# Sheet1.net
KiCad netlist of a schematic drawn in Altium Designer
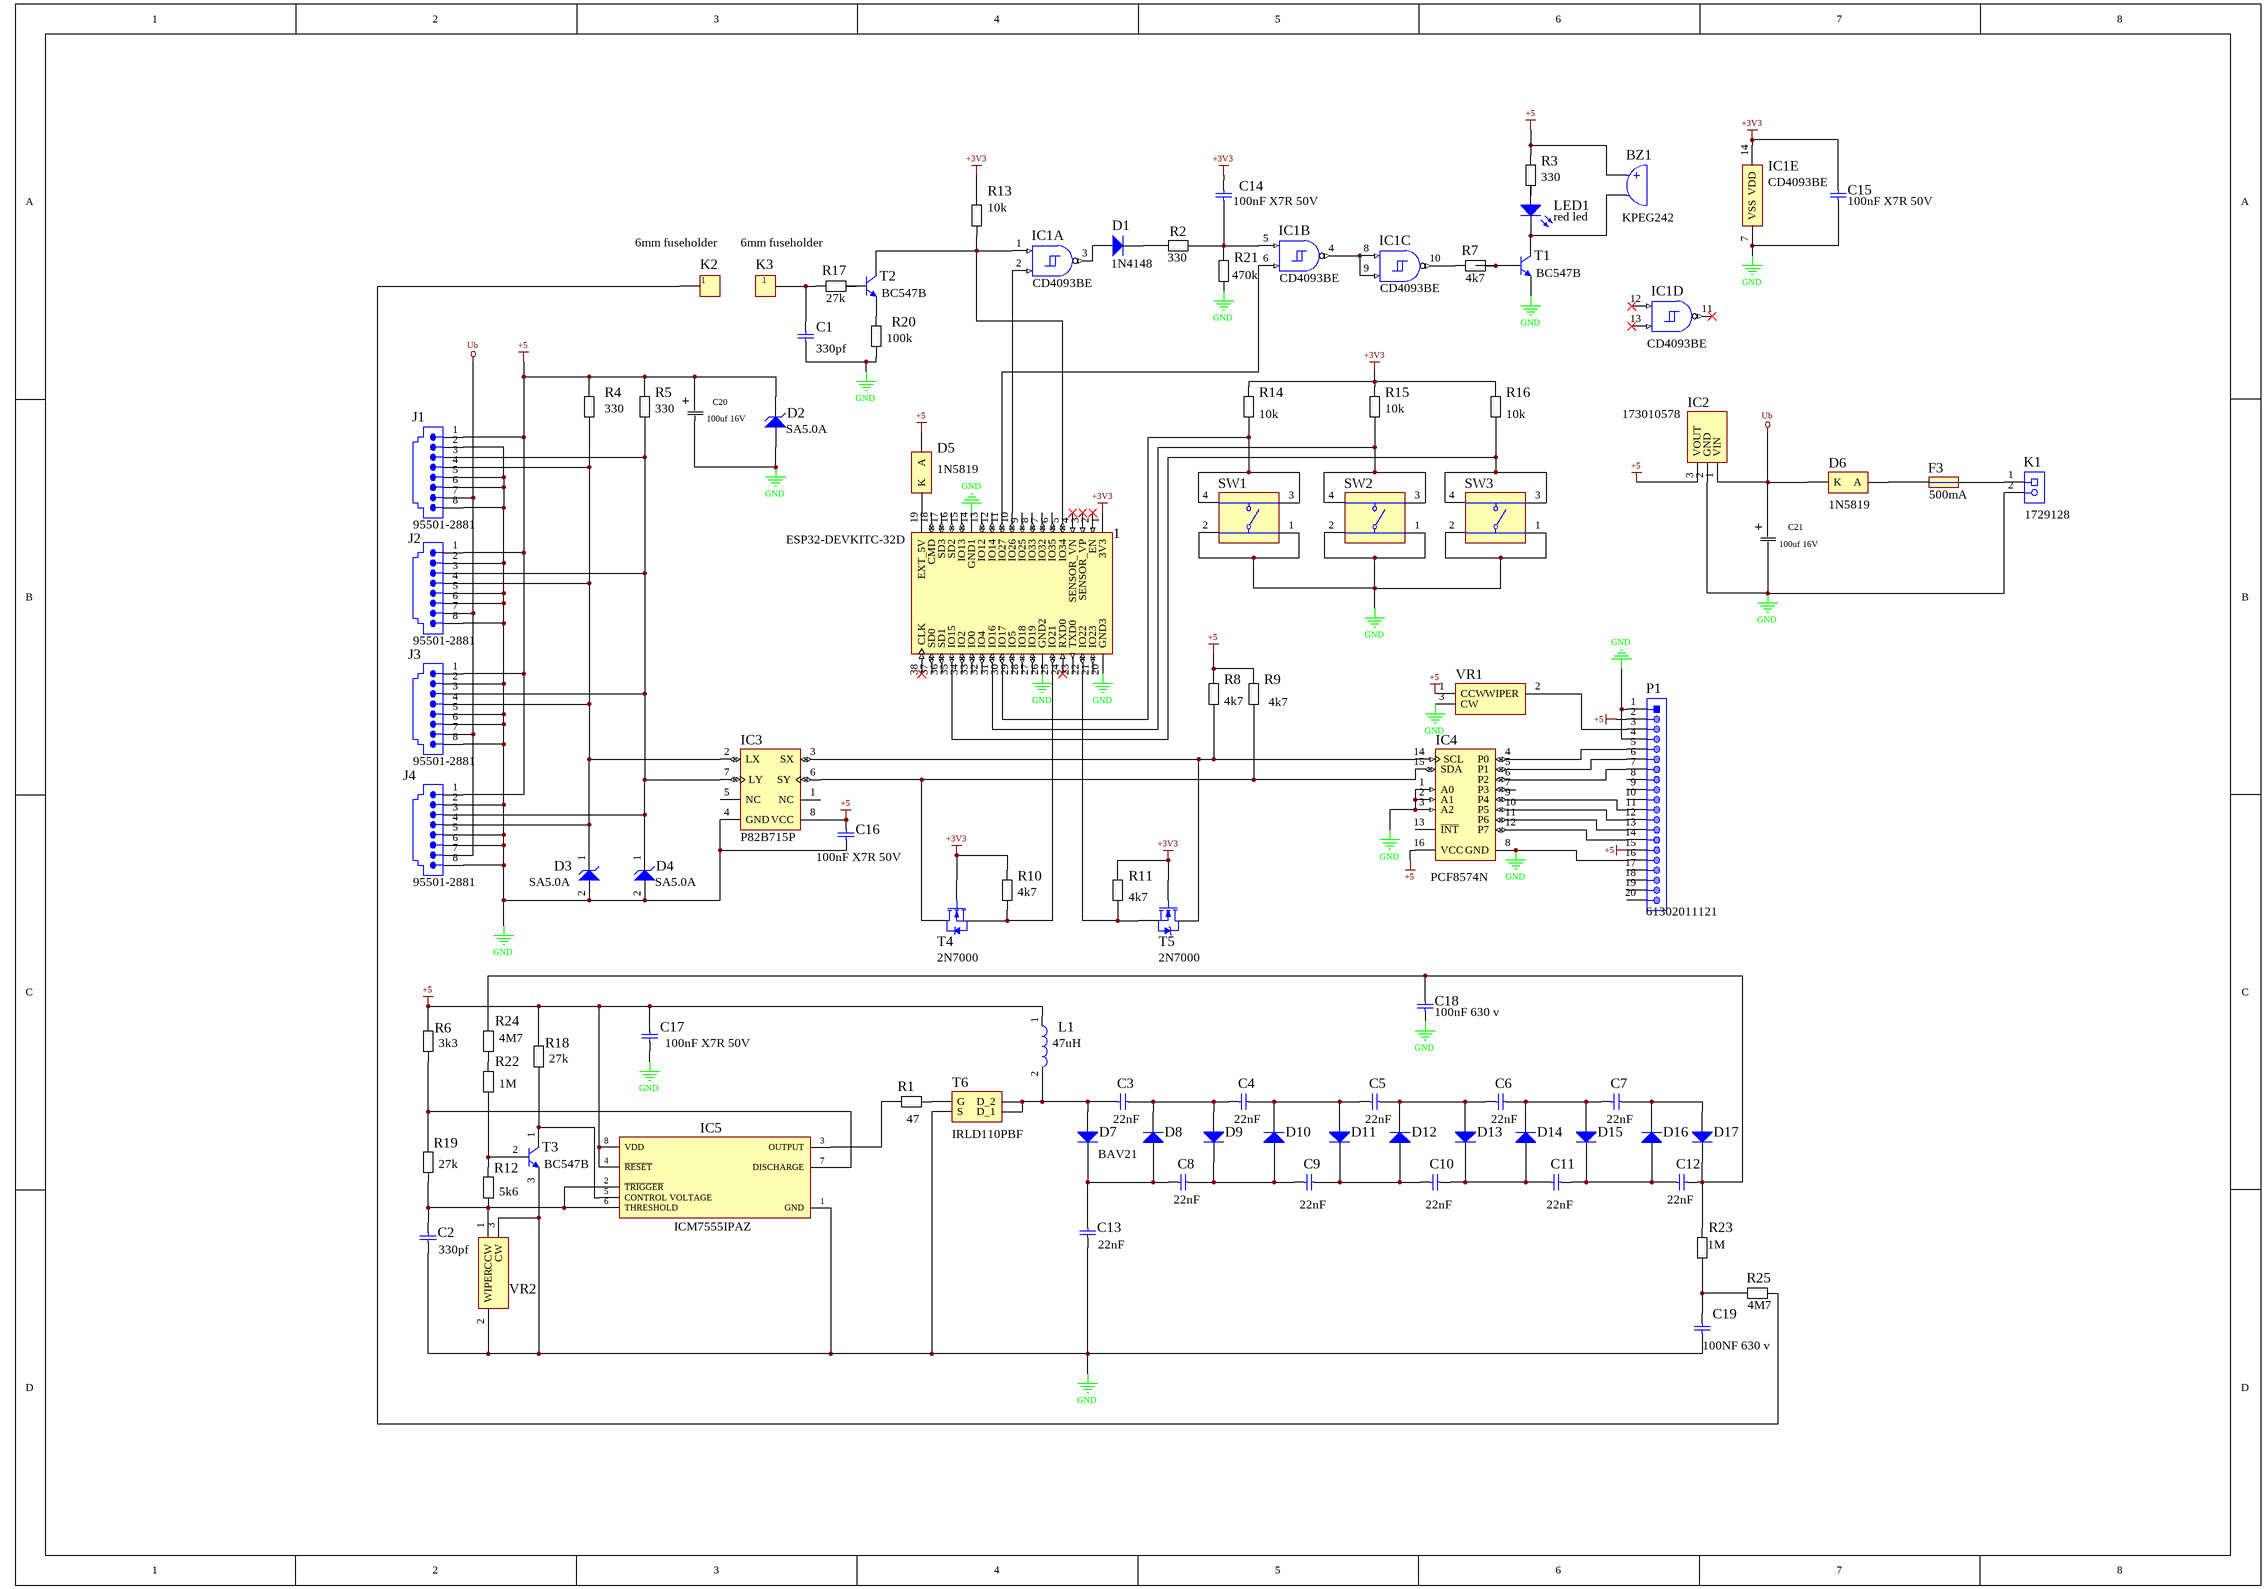
[diagram p0: Sheet1.SchDoc]

(export (version "E")
  (design (tool "Eeschema 10.0.6"))
  (components
    (comp (ref "1")
      (value "ESP32-DEVKITC-32D")
      (footprint "MODULE_ESP32-DEVKITC-32D")
      (description "EVAL BOARD FOR ESP-WROOM-32")
      (fields (field (name "MF") "Espressif Systems"))
      (libsource (lib "ESP32-DEVKITC-32D") (part "ESP32-DEVKITC-32D"))
    )
    (comp (ref "BZ1")
      (value "KPEG242")
      (footprint "KINGS-KPEG242-2")
      (description "Piezo Indicator, 4100 Hz, 3 to 16 V, -20 to 70 degC, 2-Pin THD, RoHS")
      (fields (field (name "PARTNUMBER") "KPE-242") (field (name "MANUFACTURER") "KingstateElectronicsCorp."))
      (libsource (lib "Altium Content Vault") (part "KINGS-KPEG242-2"))
    )
    (comp (ref "C1")
      (value "330pf")
      (footprint "CAPC2013X94X50ML20T25")
      (description "Chip Capacitor, Ceramic, 330 pF, 10%, 50 V, 0805, RoHS, Tape and Reel")
      (fields (field (name "MANUFACTURER") "AVX"))
      (libsource (lib "Altium Content Vault") (part "CAP-NP-2"))
    )
    (comp (ref "C2")
      (value "330pf")
      (footprint "CAPC2013X94X50ML20T25")
      (description "Chip Capacitor, Ceramic, 330 pF, 10%, 50 V, 0805, RoHS, Tape and Reel")
      (fields (field (name "MANUFACTURER") "AVX"))
      (libsource (lib "Altium Content Vault") (part "CAP-NP-2"))
    )
    (comp (ref "C3")
      (value "22nF")
      (footprint "VISH-BFC233820104-2_V")
      (fields (field (name "PARTNUMBER") "BFC233820104") (field (name "MANUFACTURER") "Vishay Semiconductor"))
      (libsource (lib "Altium Content Vault") (part "VISH-CAP-NP-2"))
    )
    (comp (ref "C4")
      (value "22nF")
      (footprint "VISH-BFC233820104-2_V")
      (fields (field (name "PARTNUMBER") "BFC233820104") (field (name "MANUFACTURER") "Vishay Semiconductor"))
      (libsource (lib "Altium Content Vault") (part "VISH-CAP-NP-2"))
    )
    (comp (ref "C5")
      (value "22nF")
      (footprint "VISH-BFC233820104-2_V")
      (fields (field (name "PARTNUMBER") "BFC233820104") (field (name "MANUFACTURER") "Vishay Semiconductor"))
      (libsource (lib "Altium Content Vault") (part "VISH-CAP-NP-2"))
    )
    (comp (ref "C6")
      (value "22nF")
      (footprint "VISH-BFC233820104-2_V")
      (fields (field (name "PARTNUMBER") "BFC233820104") (field (name "MANUFACTURER") "Vishay Semiconductor"))
      (libsource (lib "Altium Content Vault") (part "VISH-CAP-NP-2"))
    )
    (comp (ref "C7")
      (value "22nF")
      (footprint "VISH-BFC233820104-2_V")
      (fields (field (name "PARTNUMBER") "BFC233820104") (field (name "MANUFACTURER") "Vishay Semiconductor"))
      (libsource (lib "Altium Content Vault") (part "VISH-CAP-NP-2"))
    )
    (comp (ref "C8")
      (value "22nF")
      (footprint "VISH-BFC233820104-2_V")
      (fields (field (name "PARTNUMBER") "BFC233820104") (field (name "MANUFACTURER") "Vishay Semiconductor"))
      (libsource (lib "Altium Content Vault") (part "VISH-CAP-NP-2"))
    )
    (comp (ref "C9")
      (value "22nF")
      (footprint "VISH-BFC233820104-2_V")
      (fields (field (name "PARTNUMBER") "BFC233820104") (field (name "MANUFACTURER") "Vishay Semiconductor"))
      (libsource (lib "Altium Content Vault") (part "VISH-CAP-NP-2"))
    )
    (comp (ref "C10")
      (value "22nF")
      (footprint "VISH-BFC233820104-2_V")
      (fields (field (name "PARTNUMBER") "BFC233820104") (field (name "MANUFACTURER") "Vishay Semiconductor"))
      (libsource (lib "Altium Content Vault") (part "VISH-CAP-NP-2"))
    )
    (comp (ref "C11")
      (value "22nF")
      (footprint "VISH-BFC233820104-2_V")
      (fields (field (name "PARTNUMBER") "BFC233820104") (field (name "MANUFACTURER") "Vishay Semiconductor"))
      (libsource (lib "Altium Content Vault") (part "VISH-CAP-NP-2"))
    )
    (comp (ref "C12")
      (value "22nF")
      (footprint "VISH-BFC233820104-2_V")
      (fields (field (name "PARTNUMBER") "BFC233820104") (field (name "MANUFACTURER") "Vishay Semiconductor"))
      (libsource (lib "Altium Content Vault") (part "VISH-CAP-NP-2"))
    )
    (comp (ref "C13")
      (value "22nF")
      (footprint "VISH-BFC233820104-2_V")
      (fields (field (name "PARTNUMBER") "BFC233820104") (field (name "MANUFACTURER") "Vishay Semiconductor"))
      (libsource (lib "Altium Content Vault") (part "VISH-CAP-NP-2"))
    )
    (comp (ref "C14")
      (value "100nF X7R 50V")
      (footprint "CAPC2013X94X50ML20T25")
      (description "Chip Capacitor, Ceramic, 0.1 uF, 10%, 50 V, 0805, RoHS, Tape and Reel")
      (fields (field (name "MANUFACTURER") "AVX"))
      (libsource (lib "Altium Content Vault") (part "CAP-NP-2"))
    )
    (comp (ref "C15")
      (value "100nF X7R 50V")
      (footprint "CAPC2013X94X50ML20T25")
      (description "Chip Capacitor, Ceramic, 0.1 uF, 10%, 50 V, 0805, RoHS, Tape and Reel")
      (fields (field (name "MANUFACTURER") "AVX"))
      (libsource (lib "Altium Content Vault") (part "CAP-NP-2"))
    )
    (comp (ref "C16")
      (value "100nF X7R 50V")
      (footprint "CAPC2013X94X50ML20T25")
      (description "Chip Capacitor, Ceramic, 0.1 uF, 10%, 50 V, 0805, RoHS, Tape and Reel")
      (fields (field (name "MANUFACTURER") "AVX"))
      (libsource (lib "Altium Content Vault") (part "CAP-NP-2"))
    )
    (comp (ref "C17")
      (value "100nF X7R 50V")
      (footprint "CAPC2013X94X50ML20T25")
      (description "Chip Capacitor, Ceramic, 0.1 uF, 10%, 50 V, 0805, RoHS, Tape and Reel")
      (fields (field (name "MANUFACTURER") "AVX"))
      (libsource (lib "Altium Content Vault") (part "CAP-NP-2"))
    )
    (comp (ref "C18")
      (value "100nF 630 v")
      (footprint "CAPC1812(4532)125_M")
      (description "CAP 470nF 50V ±10% 1812 (4532 Metric) Thickness 1.25mm SMD")
      (fields (field (name "TOLERANCE") "Â±10%"))
      (libsource (lib "Altium Content Vault") (part "CAP"))
    )
    (comp (ref "C19")
      (value "100NF 630 v")
      (footprint "CAPC1812(4532)125_M")
      (description "CAP 470nF 50V ±10% 1812 (4532 Metric) Thickness 1.25mm SMD")
      (fields (field (name "TOLERANCE") "Â±10%"))
      (libsource (lib "Altium Content Vault") (part "CAP"))
    )
    (comp (ref "C20")
      (value "100uf 16V")
      (footprint "100uf 16V elco")
      (libsource (lib "Schlib2") (part "Component_1"))
    )
    (comp (ref "C21")
      (value "100uf 16V")
      (footprint "100uf 16V elco")
      (libsource (lib "Schlib2") (part "Component_1"))
    )
    (comp (ref "D1")
      (value "1N4148")
      (footprint "NXP-SOD27-2_V")
      (description "High-speed Diode, 100 V, 450 mA, 2-Pin SOD27, RoHS")
      (fields (field (name "MANUFACTURER") "NXP Semiconductors"))
      (libsource (lib "Altium Content Vault") (part "NXP-A1K2-2"))
    )
    (comp (ref "D2")
      (value "SA5.0A")
      (footprint "ONSC-AXIAL_LEAD-2-59AA-01_P")
      (fields (field (name "MANUFACTURER") "On Semiconductor"))
      (libsource (lib "Altium Content Vault") (part "ONSC-K1A2-2"))
    )
    (comp (ref "D3")
      (value "SA5.0A")
      (footprint "ONSC-AXIAL_LEAD-2-59AA-01_P")
      (fields (field (name "MANUFACTURER") "On Semiconductor"))
      (libsource (lib "") (part "ONSC-K1A2-2_1"))
    )
    (comp (ref "D4")
      (value "SA5.0A")
      (footprint "ONSC-AXIAL_LEAD-2-59AA-01_P")
      (fields (field (name "MANUFACTURER") "On Semiconductor"))
      (libsource (lib "") (part "ONSC-K1A2-2_1"))
    )
    (comp (ref "D5")
      (value "1N5819")
      (footprint "ONSC-AXIAL_LEAD-2-59-10_P")
      (description "Rectifier, 2-Pin Axial_Lead, Pb-Free, Bulk Bag")
      (fields (field (name "MANUFACTURER") "On Semiconductor"))
      (libsource (lib "Altium Content Vault") (part "ONSC-D-K1A2-2_A"))
    )
    (comp (ref "D6")
      (value "1N5819")
      (footprint "ONSC-AXIAL_LEAD-2-59-10_P")
      (description "Rectifier, 2-Pin Axial_Lead, Pb-Free, Bulk Bag")
      (fields (field (name "MANUFACTURER") "On Semiconductor"))
      (libsource (lib "") (part "ONSC-D-K1A2-2_A_1"))
    )
    (comp (ref "D7")
      (value "BAV21")
      (footprint "MCSM-DO-35-2")
      (description "BAV21TR Diode 250V 0.2A DO35")
      (fields (field (name "PARTNUMBER") "1N4148-1") (field (name "MANUFACTURER") "Microsemi"))
      (libsource (lib "Altium Content Vault") (part "D-AK-2"))
    )
    (comp (ref "D8")
      (value "BAV21")
      (footprint "MCSM-DO-35-2")
      (description "BAV21TR Diode 250V 0.2A DO35")
      (fields (field (name "PARTNUMBER") "1N4148-1") (field (name "MANUFACTURER") "Microsemi"))
      (libsource (lib "Altium Content Vault") (part "D-AK-2"))
    )
    (comp (ref "D9")
      (value "BAV21")
      (footprint "MCSM-DO-35-2")
      (description "BAV21TR Diode 250V 0.2A DO35")
      (fields (field (name "PARTNUMBER") "1N4148-1") (field (name "MANUFACTURER") "Microsemi"))
      (libsource (lib "Altium Content Vault") (part "D-AK-2"))
    )
    (comp (ref "D10")
      (value "BAV21")
      (footprint "MCSM-DO-35-2")
      (description "BAV21TR Diode 250V 0.2A DO35")
      (fields (field (name "PARTNUMBER") "1N4148-1") (field (name "MANUFACTURER") "Microsemi"))
      (libsource (lib "Altium Content Vault") (part "D-AK-2"))
    )
    (comp (ref "D11")
      (value "BAV21")
      (footprint "MCSM-DO-35-2")
      (description "BAV21TR Diode 250V 0.2A DO35")
      (fields (field (name "PARTNUMBER") "1N4148-1") (field (name "MANUFACTURER") "Microsemi"))
      (libsource (lib "Altium Content Vault") (part "D-AK-2"))
    )
    (comp (ref "D12")
      (value "BAV21")
      (footprint "MCSM-DO-35-2")
      (description "BAV21TR Diode 250V 0.2A DO35")
      (fields (field (name "PARTNUMBER") "1N4148-1") (field (name "MANUFACTURER") "Microsemi"))
      (libsource (lib "Altium Content Vault") (part "D-AK-2"))
    )
    (comp (ref "D13")
      (value "BAV21")
      (footprint "MCSM-DO-35-2")
      (description "BAV21TR Diode 250V 0.2A DO35")
      (fields (field (name "PARTNUMBER") "1N4148-1") (field (name "MANUFACTURER") "Microsemi"))
      (libsource (lib "Altium Content Vault") (part "D-AK-2"))
    )
    (comp (ref "D14")
      (value "BAV21")
      (footprint "MCSM-DO-35-2")
      (description "BAV21TR Diode 250V 0.2A DO35")
      (fields (field (name "PARTNUMBER") "1N4148-1") (field (name "MANUFACTURER") "Microsemi"))
      (libsource (lib "Altium Content Vault") (part "D-AK-2"))
    )
    (comp (ref "D15")
      (value "BAV21")
      (footprint "MCSM-DO-35-2")
      (description "BAV21TR Diode 250V 0.2A DO35")
      (fields (field (name "PARTNUMBER") "1N4148-1") (field (name "MANUFACTURER") "Microsemi"))
      (libsource (lib "Altium Content Vault") (part "D-AK-2"))
    )
    (comp (ref "D16")
      (value "BAV21")
      (footprint "MCSM-DO-35-2")
      (description "BAV21TR Diode 250V 0.2A DO35")
      (fields (field (name "PARTNUMBER") "1N4148-1") (field (name "MANUFACTURER") "Microsemi"))
      (libsource (lib "Altium Content Vault") (part "D-AK-2"))
    )
    (comp (ref "D17")
      (value "BAV21")
      (footprint "MCSM-DO-35-2")
      (description "BAV21TR Diode 250V 0.2A DO35")
      (fields (field (name "PARTNUMBER") "1N4148-1") (field (name "MANUFACTURER") "Microsemi"))
      (libsource (lib "Altium Content Vault") (part "D-AK-2"))
    )
    (comp (ref "F3")
      (value "500mA")
      (footprint "SamacSys:39211000000")
      (description "Fuse")
      (fields
        (field (name "MANUFACTURER_PART_NUMBER") "39211000000")
        (field (name "MOUSER PART NUMBER") "576-3921100000")
      )
      (libsource (lib "SamacSys") (part "39211000000"))
    )
    (comp (ref "IC1")
      (value "CD4093BE")
      (footprint "N0014A")
      (description "CMOS Quad 2-Input NAND Schmitt Triggers, N0014A, TUBE")
      (fields
        (field (name "MANUFACTURER") "Texas Instruments")
        (field (name "GENERIC PART NUMBER") "CD4093B")
      )
      (libsource (lib "") (part "TI-NAND-4-2IN-14_A-SCHMITT_1"))
    )
    (comp (ref "IC2")
      (value "173010578")
      (footprint "SamacSys:173010578")
      (description "Undefined or Miscellaneous")
      (fields (field (name "MOUSER2 PART NUMBER") "710-173010578"))
      (libsource (lib "SamacSys") (part "173010578"))
    )
    (comp (ref "IC3")
      (value "P82B715P")
      (footprint "P0008A")
      (description "I2C Bus Extender, 2 Channel Width, 3.0 to 12.0 V, -40 to 85 degC, 8-pin PDIP (P), Pb-Free (RoHS)")
      (fields (field (name "MANUFACTURER") "Texas Instruments"))
      (libsource (lib "Altium Content Vault") (part "TI-P82B715-PDIP_P-8"))
    )
    (comp (ref "IC4")
      (value "PCF8574N")
      (footprint "N0016A")
      (description "Remote 8-Bit I/O Expander for I2C-Bus, 2.5 to 6 V, -40 to 85 degC, 16-pin PDIP (N), Pb-Free (RoHS)")
      (fields (field (name "MANUFACTURER") "Texas Instruments"))
      (libsource (lib "Altium Content Vault") (part "TI-PCF8574-PDIP_N-16"))
    )
    (comp (ref "IC5")
      (value "ICM7555IPAZ")
      (footprint "Intersil_ICM7555IPAZ_0")
      (libsource (lib "IC_Intersil_ICM7555IPAZ_eec") (part "ICM7555IPAZ"))
    )
    (comp (ref "J1")
      (value "95501-2881")
      (footprint "MOLX-95501-2881_V")
      (description "Socket, PC Jack 8-Way, R/A Low-profile")
      (fields (field (name "MANUFACTURER") "Molex"))
      (libsource (lib "Altium Content Vault") (part "MOLX-95501-2881"))
    )
    (comp (ref "J2")
      (value "95501-2881")
      (footprint "MOLX-95501-2881_V")
      (description "Socket, PC Jack 8-Way, R/A Low-profile")
      (fields (field (name "MANUFACTURER") "Molex"))
      (libsource (lib "Altium Content Vault") (part "MOLX-95501-2881"))
    )
    (comp (ref "J3")
      (value "95501-2881")
      (footprint "MOLX-95501-2881_V")
      (description "Socket, PC Jack 8-Way, R/A Low-profile")
      (fields (field (name "MANUFACTURER") "Molex"))
      (libsource (lib "Altium Content Vault") (part "MOLX-95501-2881"))
    )
    (comp (ref "J4")
      (value "95501-2881")
      (footprint "MOLX-95501-2881_V")
      (description "Socket, PC Jack 8-Way, R/A Low-profile")
      (fields (field (name "MANUFACTURER") "Molex"))
      (libsource (lib "Altium Content Vault") (part "MOLX-95501-2881"))
    )
    (comp (ref "K1")
      (value "1729128")
      (footprint "PHOE-1729128-2_V")
      (description "PCB Terminal Block, 13.5 A, 400 V, 2-Pin THD, RoHS, Bulk")
      (fields (field (name "MANUFACTURER") "Phoenix Contact"))
      (libsource (lib "Altium Content Vault") (part "CN-2P-F-R2"))
    )
    (comp (ref "K2")
      (value "6mm fuseholder")
      (footprint "FP-102-MFG")
      (description "FUSE CLIP CARTRIDGE 250V 15A PCB")
      (fields
        (field (name "MANUFACTURER") "Littelfuse Inc")
        (field (name "OCTOPART") "https://octopart.com/01020071z-littelfuse-18837869")
      )
      (libsource (lib "Altium Content Vault") (part "600373309f0643ccfefc365bd0e8f7b"))
    )
    (comp (ref "K3")
      (value "6mm fuseholder")
      (footprint "FP-102-MFG")
      (description "FUSE CLIP CARTRIDGE 250V 15A PCB")
      (fields
        (field (name "MANUFACTURER") "Littelfuse Inc")
        (field (name "OCTOPART") "https://octopart.com/01020071z-littelfuse-18837869")
      )
      (libsource (lib "") (part "600373309f0643ccfefc365bd0e8f7b_1"))
    )
    (comp (ref "L1")
      (value "47uH")
      (footprint "WE-TI-LS")
      (description "Radial Leaded Wire Wound Inductor WE-TI, L = 100 µH")
      (libsource (lib "Altium Content Vault") (part "PAS-IND-INDUCTOR-2"))
    )
    (comp (ref "LED1")
      (value "red led")
      (footprint "Type 3mm")
      (description "THT LED round mono-color color lens, WL-TMRW, Super Red")
      (fields (field (name "PARTNUMBER") "151031SS06000") (field (name "MANUFACTURER") "Wuerth Elektronik"))
      (libsource (lib "Altium Content Vault") (part "WE-LED_K1A2-2"))
    )
    (comp (ref "P1")
      (value "61302011121")
      (footprint "61302011121")
      (description "THT Vertical Pin Header WR-PHD, Pitch 2.54 mm, Single Row, 20 pins")
      (fields (field (name "MANUFACTURER") "Wurth Elektronik") (field (name "PUBLISHER") "WurthElektronik"))
      (libsource (lib "Altium Content Vault") (part "WE-CN-1P-M-R20"))
    )
    (comp (ref "R1")
      (value "47")
      (footprint "FP-RC1206-IPC_C")
      (libsource (lib "") (part "1206 weerstand_3"))
    )
    (comp (ref "R2")
      (value "330")
      (footprint "FP-RC1206-IPC_C")
      (libsource (lib "") (part "1206 weerstand_1"))
    )
    (comp (ref "R3")
      (value "330")
      (footprint "FP-RC1206-IPC_C")
      (libsource (lib "") (part "1206 weerstand_2"))
    )
    (comp (ref "R4")
      (value "330")
      (footprint "FP-RC1206-IPC_C")
      (libsource (lib "Schlib1") (part "1206 weerstand"))
    )
    (comp (ref "R5")
      (value "330")
      (footprint "FP-RC1206-IPC_C")
      (libsource (lib "Schlib1") (part "1206 weerstand"))
    )
    (comp (ref "R6")
      (value "3k3")
      (footprint "FP-RC1206-IPC_C")
      (libsource (lib "Schlib1") (part "1206 weerstand"))
    )
    (comp (ref "R7")
      (value "4k7")
      (footprint "FP-RC1206-IPC_C")
      (libsource (lib "") (part "1206 weerstand_3"))
    )
    (comp (ref "R8")
      (value "4k7")
      (footprint "FP-RC1206-IPC_C")
      (libsource (lib "Schlib1") (part "1206 weerstand"))
    )
    (comp (ref "R9")
      (value "4k7")
      (footprint "FP-RC1206-IPC_C")
      (libsource (lib "Schlib1") (part "1206 weerstand"))
    )
    (comp (ref "R10")
      (value "4k7")
      (footprint "FP-RC1206-IPC_C")
      (libsource (lib "Schlib1") (part "1206 weerstand"))
    )
    (comp (ref "R11")
      (value "4k7")
      (footprint "FP-RC1206-IPC_C")
      (libsource (lib "") (part "1206 weerstand_1"))
    )
    (comp (ref "R12")
      (value "5k6")
      (footprint "FP-RC1206-IPC_C")
      (libsource (lib "Schlib1") (part "1206 weerstand"))
    )
    (comp (ref "R13")
      (value "10k")
      (footprint "FP-RC1206-IPC_C")
      (libsource (lib "") (part "1206 weerstand_2"))
    )
    (comp (ref "R14")
      (value "10k")
      (footprint "FP-RC1206-IPC_C")
      (libsource (lib "Schlib1") (part "1206 weerstand"))
    )
    (comp (ref "R15")
      (value "10k")
      (footprint "FP-RC1206-IPC_C")
      (libsource (lib "Schlib1") (part "1206 weerstand"))
    )
    (comp (ref "R16")
      (value "10k")
      (footprint "FP-RC1206-IPC_C")
      (libsource (lib "Schlib1") (part "1206 weerstand"))
    )
    (comp (ref "R17")
      (value "27k")
      (footprint "FP-RC1206-IPC_C")
      (libsource (lib "") (part "1206 weerstand_3"))
    )
    (comp (ref "R18")
      (value "27k")
      (footprint "FP-RC1206-IPC_C")
      (libsource (lib "Schlib1") (part "1206 weerstand"))
    )
    (comp (ref "R19")
      (value "27k")
      (footprint "FP-RC1206-IPC_C")
      (libsource (lib "Schlib1") (part "1206 weerstand"))
    )
    (comp (ref "R20")
      (value "100k")
      (footprint "FP-RC1206-IPC_C")
      (libsource (lib "") (part "1206 weerstand_2"))
    )
    (comp (ref "R21")
      (value "470k")
      (footprint "FP-RC1206-IPC_C")
      (libsource (lib "Schlib1") (part "1206 weerstand"))
    )
    (comp (ref "R22")
      (value "1M")
      (footprint "RES_VR25")
      (description "No Description Available")
      (fields
        (field (name "MANUFACTURER_PART_NUMBER") "VR25000001004JA100")
        (field (name "COPYRIGHT") "Copyright (C) 2018 Accelerated Designs. All rights reserved")
      )
      (libsource (lib "2021-03-05_17-49-49") (part "VR25000001004JA100"))
    )
    (comp (ref "R23")
      (value "1M")
      (footprint "RES_VR25")
      (description "No Description Available")
      (fields
        (field (name "MANUFACTURER_PART_NUMBER") "VR25000001004JA100")
        (field (name "COPYRIGHT") "Copyright (C) 2018 Accelerated Designs. All rights reserved")
      )
      (libsource (lib "2021-03-05_17-49-49") (part "VR25000001004JA100"))
    )
    (comp (ref "R24")
      (value "4M7")
      (footprint "RES_VR25")
      (description "No Description Available")
      (fields
        (field (name "MANUFACTURER_PART_NUMBER") "VR25000001004JA100")
        (field (name "COPYRIGHT") "Copyright (C) 2018 Accelerated Designs. All rights reserved")
      )
      (libsource (lib "2021-03-05_17-49-49") (part "VR25000001004JA100"))
    )
    (comp (ref "R25")
      (value "4M7")
      (footprint "RES_VR25")
      (description "No Description Available")
      (fields
        (field (name "MANUFACTURER_PART_NUMBER") "VR25000001004JA100")
        (field (name "COPYRIGHT") "Copyright (C) 2018 Accelerated Designs. All rights reserved")
      )
      (libsource (lib "") (part "VR25000001004JA100_1"))
    )
    (comp (ref "SW1")
      (value "tactile switch 10mm")
      (footprint "TECO-1825910-6_V")
      (description "Tact Switch, SPST-NO, 0.05 A, -35 to 85 degC, 4-Pin THD, RoHS, Bulk")
      (fields (field (name "PART NO") "1825910-6") (field (name "MANUFACTURER") "TE Connectivity"))
      (libsource (lib "Altium Content Vault") (part "SW-SPST-4_A"))
    )
    (comp (ref "SW2")
      (value "tactile switch 10mm")
      (footprint "TECO-1825910-6_V")
      (description "Tact Switch, SPST-NO, 0.05 A, -35 to 85 degC, 4-Pin THD, RoHS, Bulk")
      (fields (field (name "PART NO") "1825910-6") (field (name "MANUFACTURER") "TE Connectivity"))
      (libsource (lib "Altium Content Vault") (part "SW-SPST-4_A"))
    )
    (comp (ref "SW3")
      (value "tactile switch 10mm")
      (footprint "TECO-1825910-6_V")
      (description "Tact Switch, SPST-NO, 0.05 A, -35 to 85 degC, 4-Pin THD, RoHS, Bulk")
      (fields (field (name "PART NO") "1825910-6") (field (name "MANUFACTURER") "TE Connectivity"))
      (libsource (lib "Altium Content Vault") (part "SW-SPST-4_A"))
    )
    (comp (ref "T1")
      (value "BC547B")
      (footprint "ONSC-TO-92-3-29-11")
      (description "Amplifier Transistor, NPN Silicon, 3-Pin TO-92, Bulk Box")
      (fields (field (name "MANUFACTURER") "On Semiconductor"))
      (libsource (lib "Altium Content Vault") (part "ONSC-NPN-C1B2E3-3"))
    )
    (comp (ref "T2")
      (value "BC547B")
      (footprint "ONSC-TO-92-3-29-11")
      (description "Amplifier Transistor, NPN Silicon, 3-Pin TO-92, Bulk Box")
      (fields (field (name "MANUFACTURER") "On Semiconductor"))
      (libsource (lib "Altium Content Vault") (part "ONSC-NPN-C1B2E3-3"))
    )
    (comp (ref "T3")
      (value "BC547B")
      (footprint "ONSC-TO-92-3-29-11")
      (description "Amplifier Transistor, NPN Silicon, 3-Pin TO-92, Bulk Box")
      (fields (field (name "MANUFACTURER") "On Semiconductor"))
      (libsource (lib "") (part "ONSC-NPN-C1B2E3-3_1"))
    )
    (comp (ref "T4")
      (value "2N7000")
      (footprint "ONSC-TO-92-3-29-11")
      (description "Small Signal MOSFET, 200 mA, 60 V, N-Channel, 3-Pin TO-92, Bulk Box")
      (fields (field (name "MANUFACTURER") "On Semiconductor"))
      (libsource (lib "Altium Content Vault") (part "ONSC-NMOS-S1G2D3-3"))
    )
    (comp (ref "T5")
      (value "2N7000")
      (footprint "ONSC-TO-92-3-29-11")
      (description "Small Signal MOSFET, 200 mA, 60 V, N-Channel, 3-Pin TO-92, Bulk Box")
      (fields (field (name "MANUFACTURER") "On Semiconductor"))
      (libsource (lib "Altium Content Vault") (part "ONSC-NMOS-S1G2D3-3"))
    )
    (comp (ref "T6")
      (value "IRLD110PBF")
      (footprint "SamacSys:DIP920W60P254L490H337Q4N")
      (description "MOSFET (N-Channel)")
      (fields (field (name "MOUSER PART NUMBER") "844-IRLD110PBF"))
      (libsource (lib "SamacSys") (part "IRLD110PBF"))
    )
    (comp (ref "VR1")
      (value "~")
      (footprint "RM065102")
      (description "Variable Resistor")
      (fields (field (name "MANUFACTURER_PART_NUMBER") "RM-065-102"))
      (libsource (lib "") (part "RM-065-102_1"))
    )
    (comp (ref "VR2")
      (value "RM-065-102")
      (footprint "SamacSys:RM065102")
      (description "Variable Resistor")
      (libsource (lib "SamacSys") (part "RM-065-102"))
    )
  )
  (nets
    (net (code "1") (name "+3V3") (class "Default")
      (node (ref "1") (pin "1") (pinfunction "3V3_1") (pintype "power_in"))
      (node (ref "C14") (pin "2") (pinfunction "2_2") (pintype "passive"))
      (node (ref "C15") (pin "2") (pinfunction "2_2") (pintype "passive"))
      (node (ref "IC1") (pin "14") (pinfunction "VDD_14") (pintype "power_in"))
      (node (ref "R10") (pin "2") (pintype "passive"))
      (node (ref "R11") (pin "2") (pintype "passive"))
      (node (ref "R13") (pin "1") (pintype "passive"))
      (node (ref "R14") (pin "2") (pintype "passive"))
      (node (ref "R15") (pin "2") (pintype "passive"))
      (node (ref "R16") (pin "2") (pintype "passive"))
      (node (ref "T4") (pin "2") (pinfunction "G_2") (pintype "passive"))
      (node (ref "T5") (pin "2") (pinfunction "G_2") (pintype "passive"))
    )
    (net (code "2") (name "+5") (class "Default")
      (node (ref "BZ1") (pin "1") (pinfunction "1_1") (pintype "passive"))
      (node (ref "C16") (pin "2") (pinfunction "2_2") (pintype "passive"))
      (node (ref "C17") (pin "2") (pinfunction "2_2") (pintype "passive"))
      (node (ref "D2") (pin "1") (pinfunction "K_1") (pintype "passive"))
      (node (ref "D5") (pin "2") (pinfunction "A_2") (pintype "passive"))
      (node (ref "IC2") (pin "3") (pinfunction "VOUT_3") (pintype "passive"))
      (node (ref "IC3") (pin "8") (pinfunction "VCC_8") (pintype "power_in"))
      (node (ref "IC4") (pin "16") (pinfunction "VCC_16") (pintype "power_in"))
      (node (ref "IC5") (pin "4") (pinfunction "~{RESET}_4") (pintype "passive"))
      (node (ref "IC5") (pin "8") (pinfunction "VDD_8") (pintype "passive"))
      (node (ref "J1") (pin "1") (pinfunction "1_1") (pintype "passive"))
      (node (ref "J2") (pin "1") (pinfunction "1_1") (pintype "passive"))
      (node (ref "J3") (pin "1") (pinfunction "1_1") (pintype "passive"))
      (node (ref "J4") (pin "1") (pinfunction "1_1") (pintype "passive"))
      (node (ref "L1") (pin "1") (pinfunction "1_1") (pintype "passive"))
      (node (ref "P1") (pin "15") (pinfunction "15_15") (pintype "passive"))
      (node (ref "P1") (pin "2") (pinfunction "2_2") (pintype "passive"))
      (node (ref "R18") (pin "2") (pintype "passive"))
      (node (ref "R3") (pin "1") (pintype "passive"))
      (node (ref "R4") (pin "2") (pintype "passive"))
      (node (ref "R5") (pin "2") (pintype "passive"))
      (node (ref "R6") (pin "2") (pintype "passive"))
      (node (ref "R8") (pin "2") (pintype "passive"))
      (node (ref "R9") (pin "2") (pintype "passive"))
      (node (ref "VR1") (pin "1") (pinfunction "CCW_1") (pintype "passive"))
    )
    (net (code "3") (name "GND") (class "Default")
      (node (ref "1") (pin "14") (pinfunction "GND1_14") (pintype "power_in"))
      (node (ref "1") (pin "20") (pinfunction "GND3_20") (pintype "power_in"))
      (node (ref "1") (pin "26") (pinfunction "GND2_26") (pintype "power_in"))
      (node (ref "C1") (pin "1") (pinfunction "1_1") (pintype "passive"))
      (node (ref "C13") (pin "1") (pinfunction "1_1") (pintype "passive"))
      (node (ref "C15") (pin "1") (pinfunction "1_1") (pintype "passive"))
      (node (ref "C16") (pin "1") (pinfunction "1_1") (pintype "passive"))
      (node (ref "C17") (pin "1") (pinfunction "1_1") (pintype "passive"))
      (node (ref "C18") (pin "1") (pinfunction "1_1") (pintype "passive"))
      (node (ref "C19") (pin "1") (pinfunction "1_1") (pintype "passive"))
      (node (ref "C2") (pin "1") (pinfunction "1_1") (pintype "passive"))
      (node (ref "D2") (pin "2") (pinfunction "A_2") (pintype "passive"))
      (node (ref "D3") (pin "2") (pinfunction "A_2") (pintype "passive"))
      (node (ref "D4") (pin "2") (pinfunction "A_2") (pintype "passive"))
      (node (ref "IC1") (pin "7") (pinfunction "VSS_7") (pintype "power_in"))
      (node (ref "IC2") (pin "2") (pinfunction "GND_2") (pintype "passive"))
      (node (ref "IC3") (pin "4") (pinfunction "GND_4") (pintype "power_in"))
      (node (ref "IC4") (pin "1") (pinfunction "A0_1") (pintype "input"))
      (node (ref "IC4") (pin "2") (pinfunction "A1_2") (pintype "input"))
      (node (ref "IC4") (pin "3") (pinfunction "A2_3") (pintype "input"))
      (node (ref "IC4") (pin "8") (pinfunction "GND_8") (pintype "power_in"))
      (node (ref "IC5") (pin "1") (pinfunction "GND_1") (pintype "passive"))
      (node (ref "J1") (pin "2") (pinfunction "2_2") (pintype "passive"))
      (node (ref "J1") (pin "5") (pinfunction "5_5") (pintype "passive"))
      (node (ref "J1") (pin "6") (pinfunction "6_6") (pintype "passive"))
      (node (ref "J1") (pin "8") (pinfunction "8_8") (pintype "passive"))
      (node (ref "J2") (pin "2") (pinfunction "2_2") (pintype "passive"))
      (node (ref "J2") (pin "5") (pinfunction "5_5") (pintype "passive"))
      (node (ref "J2") (pin "6") (pinfunction "6_6") (pintype "passive"))
      (node (ref "J2") (pin "8") (pinfunction "8_8") (pintype "passive"))
      (node (ref "J3") (pin "2") (pinfunction "2_2") (pintype "passive"))
      (node (ref "J3") (pin "5") (pinfunction "5_5") (pintype "passive"))
      (node (ref "J3") (pin "6") (pinfunction "6_6") (pintype "passive"))
      (node (ref "J3") (pin "8") (pinfunction "8_8") (pintype "passive"))
      (node (ref "J4") (pin "2") (pinfunction "2_2") (pintype "passive"))
      (node (ref "J4") (pin "5") (pinfunction "5_5") (pintype "passive"))
      (node (ref "J4") (pin "6") (pinfunction "6_6") (pintype "passive"))
      (node (ref "J4") (pin "8") (pinfunction "8_8") (pintype "passive"))
      (node (ref "K1") (pin "2") (pinfunction "2_2") (pintype "passive"))
      (node (ref "P1") (pin "1") (pinfunction "1_1") (pintype "passive"))
      (node (ref "P1") (pin "16") (pinfunction "16_16") (pintype "passive"))
      (node (ref "P1") (pin "4") (pinfunction "4_4") (pintype "passive"))
      (node (ref "R20") (pin "2") (pintype "passive"))
      (node (ref "R21") (pin "1") (pintype "passive"))
      (node (ref "SW1") (pin "1") (pinfunction "1_1") (pintype "passive"))
      (node (ref "SW1") (pin "2") (pinfunction "2_2") (pintype "passive"))
      (node (ref "SW2") (pin "1") (pinfunction "1_1") (pintype "passive"))
      (node (ref "SW2") (pin "2") (pinfunction "2_2") (pintype "passive"))
      (node (ref "SW3") (pin "1") (pinfunction "1_1") (pintype "passive"))
      (node (ref "SW3") (pin "2") (pinfunction "2_2") (pintype "passive"))
      (node (ref "T1") (pin "3") (pinfunction "E_3") (pintype "passive"))
      (node (ref "T3") (pin "3") (pinfunction "E_3") (pintype "passive"))
      (node (ref "T6") (pin "2") (pinfunction "S_2") (pintype "passive"))
      (node (ref "VR1") (pin "3") (pinfunction "CW_3") (pintype "passive"))
      (node (ref "VR2") (pin "2") (pinfunction "WIPER_2") (pintype "passive"))
      (node (ref "VR2") (pin "3") (pinfunction "CW_3") (pintype "passive"))
    )
    (net (code "4") (name "Net-(1-EXT_5V)") (class "Default")
      (node (ref "1") (pin "19") (pinfunction "EXT_5V_19") (pintype "power_in"))
      (node (ref "D5") (pin "1") (pinfunction "K_1") (pintype "passive"))
    )
    (net (code "5") (name "Net-(1-IO15)") (class "Default")
      (node (ref "1") (pin "35") (pinfunction "IO15_35") (pintype "bidirectional"))
      (node (ref "R16") (pin "1") (pintype "passive"))
      (node (ref "SW3") (pin "3") (pinfunction "3_3") (pintype "passive"))
      (node (ref "SW3") (pin "4") (pinfunction "4_4") (pintype "passive"))
    )
    (net (code "6") (name "Net-(1-IO16)") (class "Default")
      (node (ref "1") (pin "31") (pinfunction "IO16_31") (pintype "bidirectional"))
      (node (ref "R15") (pin "1") (pintype "passive"))
      (node (ref "SW2") (pin "3") (pinfunction "3_3") (pintype "passive"))
      (node (ref "SW2") (pin "4") (pinfunction "4_4") (pintype "passive"))
    )
    (net (code "7") (name "Net-(1-IO17)") (class "Default")
      (node (ref "1") (pin "30") (pinfunction "IO17_30") (pintype "bidirectional"))
      (node (ref "R14") (pin "1") (pintype "passive"))
      (node (ref "SW1") (pin "3") (pinfunction "3_3") (pintype "passive"))
      (node (ref "SW1") (pin "4") (pinfunction "4_4") (pintype "passive"))
    )
    (net (code "8") (name "Net-(1-IO21)") (class "Default")
      (node (ref "1") (pin "25") (pinfunction "IO21_25") (pintype "bidirectional"))
      (node (ref "R10") (pin "1") (pintype "passive"))
      (node (ref "T4") (pin "1") (pinfunction "S_1") (pintype "passive"))
    )
    (net (code "9") (name "Net-(1-IO22)") (class "Default")
      (node (ref "1") (pin "22") (pinfunction "IO22_22") (pintype "bidirectional"))
      (node (ref "R11") (pin "1") (pintype "passive"))
      (node (ref "T5") (pin "1") (pinfunction "S_1") (pintype "passive"))
    )
    (net (code "10") (name "Net-(1-IO26)") (class "Default")
      (node (ref "1") (pin "10") (pinfunction "IO26_10") (pintype "bidirectional"))
      (node (ref "IC1") (pin "2") (pinfunction "B_2") (pintype "input"))
    )
    (net (code "11") (name "Net-(1-IO27)") (class "Default")
      (node (ref "1") (pin "11") (pinfunction "IO27_11") (pintype "bidirectional"))
      (node (ref "IC1") (pin "6") (pinfunction "D_6") (pintype "input"))
    )
    (net (code "12") (name "Net-(1-IO34)") (class "Default")
      (node (ref "1") (pin "5") (pinfunction "IO34_5") (pintype "bidirectional"))
      (node (ref "IC1") (pin "1") (pinfunction "A_1") (pintype "input"))
      (node (ref "R13") (pin "2") (pintype "passive"))
      (node (ref "T2") (pin "1") (pinfunction "C_1") (pintype "passive"))
    )
    (net (code "13") (name "Net-(C1-Pad2)") (class "Default")
      (node (ref "C1") (pin "2") (pinfunction "2_2") (pintype "passive"))
      (node (ref "K3") (pin "1") (pinfunction "1_1") (pintype "passive"))
      (node (ref "R17") (pin "2") (pintype "passive"))
    )
    (net (code "14") (name "Net-(C19-Pad2)") (class "Default")
      (node (ref "C19") (pin "2") (pinfunction "2_2") (pintype "passive"))
      (node (ref "R23") (pin "1") (pintype "passive"))
      (node (ref "R25") (pin "1") (pintype "passive"))
    )
    (net (code "15") (name "Net-(D1-A)") (class "Default")
      (node (ref "D1") (pin "1") (pinfunction "A_1") (pintype "passive"))
      (node (ref "IC1") (pin "3") (pinfunction "J_3") (pintype "output"))
    )
    (net (code "16") (name "Net-(D1-K)") (class "Default")
      (node (ref "D1") (pin "2") (pinfunction "K_2") (pintype "passive"))
      (node (ref "R2") (pin "1") (pintype "passive"))
    )
    (net (code "17") (name "Net-(D3-K)") (class "Default")
      (node (ref "D3") (pin "1") (pinfunction "K_1") (pintype "passive"))
      (node (ref "IC3") (pin "2") (pinfunction "LX_2") (pintype "bidirectional"))
      (node (ref "J1") (pin "4") (pinfunction "4_4") (pintype "passive"))
      (node (ref "J2") (pin "4") (pinfunction "4_4") (pintype "passive"))
      (node (ref "J3") (pin "4") (pinfunction "4_4") (pintype "passive"))
      (node (ref "J4") (pin "4") (pinfunction "4_4") (pintype "passive"))
      (node (ref "R4") (pin "1") (pintype "passive"))
    )
    (net (code "18") (name "Net-(D4-K)") (class "Default")
      (node (ref "D4") (pin "1") (pinfunction "K_1") (pintype "passive"))
      (node (ref "IC3") (pin "7") (pinfunction "LY_7") (pintype "bidirectional"))
      (node (ref "J1") (pin "3") (pinfunction "3_3") (pintype "passive"))
      (node (ref "J2") (pin "3") (pinfunction "3_3") (pintype "passive"))
      (node (ref "J3") (pin "3") (pinfunction "3_3") (pintype "passive"))
      (node (ref "J4") (pin "3") (pinfunction "3_3") (pintype "passive"))
      (node (ref "R5") (pin "1") (pintype "passive"))
    )
    (net (code "19") (name "Net-(D6-A)") (class "Default")
      (node (ref "D6") (pin "2") (pinfunction "A_2") (pintype "passive"))
      (node (ref "F3") (pin "1") (pinfunction "1_1") (pintype "passive"))
    )
    (net (code "20") (name "Net-(D7-A)") (class "Default")
      (node (ref "C3") (pin "1") (pinfunction "1_1") (pintype "passive"))
      (node (ref "D7") (pin "1") (pinfunction "A_1") (pintype "passive"))
      (node (ref "L1") (pin "2") (pinfunction "2_2") (pintype "passive"))
      (node (ref "T6") (pin "3") (pinfunction "D_1_3") (pintype "passive"))
      (node (ref "T6") (pin "4") (pinfunction "D_2_4") (pintype "passive"))
    )
    (net (code "21") (name "Net-(D7-K)") (class "Default")
      (node (ref "C13") (pin "2") (pinfunction "2_2") (pintype "passive"))
      (node (ref "C8") (pin "1") (pinfunction "1_1") (pintype "passive"))
      (node (ref "D7") (pin "2") (pinfunction "K_2") (pintype "passive"))
      (node (ref "D8") (pin "1") (pinfunction "A_1") (pintype "passive"))
    )
    (net (code "22") (name "Net-(D8-K)") (class "Default")
      (node (ref "C3") (pin "2") (pinfunction "2_2") (pintype "passive"))
      (node (ref "C4") (pin "1") (pinfunction "1_1") (pintype "passive"))
      (node (ref "D8") (pin "2") (pinfunction "K_2") (pintype "passive"))
      (node (ref "D9") (pin "1") (pinfunction "A_1") (pintype "passive"))
    )
    (net (code "23") (name "Net-(D10-A)") (class "Default")
      (node (ref "C8") (pin "2") (pinfunction "2_2") (pintype "passive"))
      (node (ref "C9") (pin "1") (pinfunction "1_1") (pintype "passive"))
      (node (ref "D10") (pin "1") (pinfunction "A_1") (pintype "passive"))
      (node (ref "D9") (pin "2") (pinfunction "K_2") (pintype "passive"))
    )
    (net (code "24") (name "Net-(D10-K)") (class "Default")
      (node (ref "C4") (pin "2") (pinfunction "2_2") (pintype "passive"))
      (node (ref "C5") (pin "1") (pinfunction "1_1") (pintype "passive"))
      (node (ref "D10") (pin "2") (pinfunction "K_2") (pintype "passive"))
      (node (ref "D11") (pin "1") (pinfunction "A_1") (pintype "passive"))
    )
    (net (code "25") (name "Net-(D11-K)") (class "Default")
      (node (ref "C10") (pin "1") (pinfunction "1_1") (pintype "passive"))
      (node (ref "C9") (pin "2") (pinfunction "2_2") (pintype "passive"))
      (node (ref "D11") (pin "2") (pinfunction "K_2") (pintype "passive"))
      (node (ref "D12") (pin "1") (pinfunction "A_1") (pintype "passive"))
    )
    (net (code "26") (name "Net-(D12-K)") (class "Default")
      (node (ref "C5") (pin "2") (pinfunction "2_2") (pintype "passive"))
      (node (ref "C6") (pin "1") (pinfunction "1_1") (pintype "passive"))
      (node (ref "D12") (pin "2") (pinfunction "K_2") (pintype "passive"))
      (node (ref "D13") (pin "1") (pinfunction "A_1") (pintype "passive"))
    )
    (net (code "27") (name "Net-(D13-K)") (class "Default")
      (node (ref "C10") (pin "2") (pinfunction "2_2") (pintype "passive"))
      (node (ref "C11") (pin "1") (pinfunction "1_1") (pintype "passive"))
      (node (ref "D13") (pin "2") (pinfunction "K_2") (pintype "passive"))
      (node (ref "D14") (pin "1") (pinfunction "A_1") (pintype "passive"))
    )
    (net (code "28") (name "Net-(D14-K)") (class "Default")
      (node (ref "C6") (pin "2") (pinfunction "2_2") (pintype "passive"))
      (node (ref "C7") (pin "1") (pinfunction "1_1") (pintype "passive"))
      (node (ref "D14") (pin "2") (pinfunction "K_2") (pintype "passive"))
      (node (ref "D15") (pin "1") (pinfunction "A_1") (pintype "passive"))
    )
    (net (code "29") (name "Net-(D15-K)") (class "Default")
      (node (ref "C11") (pin "2") (pinfunction "2_2") (pintype "passive"))
      (node (ref "C12") (pin "1") (pinfunction "1_1") (pintype "passive"))
      (node (ref "D15") (pin "2") (pinfunction "K_2") (pintype "passive"))
      (node (ref "D16") (pin "1") (pinfunction "A_1") (pintype "passive"))
    )
    (net (code "30") (name "Net-(D16-K)") (class "Default")
      (node (ref "C7") (pin "2") (pinfunction "2_2") (pintype "passive"))
      (node (ref "D16") (pin "2") (pinfunction "K_2") (pintype "passive"))
      (node (ref "D17") (pin "1") (pinfunction "A_1") (pintype "passive"))
    )
    (net (code "31") (name "Net-(D17-K)") (class "Default")
      (node (ref "C12") (pin "2") (pinfunction "2_2") (pintype "passive"))
      (node (ref "C18") (pin "2") (pinfunction "2_2") (pintype "passive"))
      (node (ref "D17") (pin "2") (pinfunction "K_2") (pintype "passive"))
      (node (ref "R23") (pin "2") (pintype "passive"))
      (node (ref "R24") (pin "2") (pintype "passive"))
    )
    (net (code "32") (name "Net-(F3-Pad2)") (class "Default")
      (node (ref "F3") (pin "2") (pinfunction "2_2") (pintype "passive"))
      (node (ref "K1") (pin "1") (pinfunction "1_1") (pintype "passive"))
    )
    (net (code "33") (name "Net-(IC1B-C)") (class "Default")
      (node (ref "C14") (pin "1") (pinfunction "1_1") (pintype "passive"))
      (node (ref "IC1") (pin "5") (pinfunction "C_5") (pintype "input"))
      (node (ref "R2") (pin "2") (pintype "passive"))
      (node (ref "R21") (pin "2") (pintype "passive"))
    )
    (net (code "34") (name "Net-(IC1B-K)") (class "Default")
      (node (ref "IC1") (pin "4") (pinfunction "K_4") (pintype "output"))
      (node (ref "IC1") (pin "8") (pinfunction "E_8") (pintype "input"))
      (node (ref "IC1") (pin "9") (pinfunction "F_9") (pintype "input"))
    )
    (net (code "35") (name "Net-(IC1C-L)") (class "Default")
      (node (ref "IC1") (pin "10") (pinfunction "L_10") (pintype "output"))
      (node (ref "R7") (pin "2") (pintype "passive"))
    )
    (net (code "36") (name "Net-(IC3-SX)") (class "Default")
      (node (ref "IC3") (pin "3") (pinfunction "SX_3") (pintype "bidirectional"))
      (node (ref "IC4") (pin "14") (pinfunction "SCL_14") (pintype "input"))
      (node (ref "R8") (pin "1") (pintype "passive"))
      (node (ref "T5") (pin "3") (pinfunction "D_3") (pintype "passive"))
    )
    (net (code "37") (name "Net-(IC3-SY)") (class "Default")
      (node (ref "IC3") (pin "6") (pinfunction "SY_6") (pintype "bidirectional"))
      (node (ref "IC4") (pin "15") (pinfunction "SDA_15") (pintype "bidirectional"))
      (node (ref "R9") (pin "1") (pintype "passive"))
      (node (ref "T4") (pin "3") (pinfunction "D_3") (pintype "passive"))
    )
    (net (code "38") (name "Net-(IC4-P0)") (class "Default")
      (node (ref "IC4") (pin "4") (pinfunction "P0_4") (pintype "bidirectional"))
      (node (ref "P1") (pin "5") (pinfunction "5_5") (pintype "passive"))
    )
    (net (code "39") (name "Net-(IC4-P1)") (class "Default")
      (node (ref "IC4") (pin "5") (pinfunction "P1_5") (pintype "bidirectional"))
      (node (ref "P1") (pin "6") (pinfunction "6_6") (pintype "passive"))
    )
    (net (code "40") (name "Net-(IC4-P2)") (class "Default")
      (node (ref "IC4") (pin "6") (pinfunction "P2_6") (pintype "bidirectional"))
      (node (ref "P1") (pin "7") (pinfunction "7_7") (pintype "passive"))
    )
    (net (code "41") (name "Net-(IC4-P4)") (class "Default")
      (node (ref "IC4") (pin "9") (pinfunction "P4_9") (pintype "bidirectional"))
      (node (ref "P1") (pin "11") (pinfunction "11_11") (pintype "passive"))
    )
    (net (code "42") (name "Net-(IC4-P5)") (class "Default")
      (node (ref "IC4") (pin "10") (pinfunction "P5_10") (pintype "bidirectional"))
      (node (ref "P1") (pin "12") (pinfunction "12_12") (pintype "passive"))
    )
    (net (code "43") (name "Net-(IC4-P6)") (class "Default")
      (node (ref "IC4") (pin "11") (pinfunction "P6_11") (pintype "bidirectional"))
      (node (ref "P1") (pin "13") (pinfunction "13_13") (pintype "passive"))
    )
    (net (code "44") (name "Net-(IC4-P7)") (class "Default")
      (node (ref "IC4") (pin "12") (pinfunction "P7_12") (pintype "bidirectional"))
      (node (ref "P1") (pin "14") (pinfunction "14_14") (pintype "passive"))
    )
    (net (code "45") (name "Net-(IC5-CONTROL_VOLTAGE)") (class "Default")
      (node (ref "IC5") (pin "5") (pinfunction "CONTROL_VOLTAGE_5") (pintype "passive"))
      (node (ref "R18") (pin "1") (pintype "passive"))
      (node (ref "T3") (pin "1") (pinfunction "C_1") (pintype "passive"))
    )
    (net (code "46") (name "Net-(IC5-DISCHARGE)") (class "Default")
      (node (ref "IC5") (pin "7") (pinfunction "DISCHARGE_7") (pintype "passive"))
      (node (ref "R19") (pin "2") (pintype "passive"))
      (node (ref "R6") (pin "1") (pintype "passive"))
    )
    (net (code "47") (name "Net-(IC5-OUTPUT)") (class "Default")
      (node (ref "IC5") (pin "3") (pinfunction "OUTPUT_3") (pintype "passive"))
      (node (ref "R1") (pin "2") (pintype "passive"))
    )
    (net (code "48") (name "Net-(IC5-THRESHOLD)") (class "Default")
      (node (ref "C2") (pin "2") (pinfunction "2_2") (pintype "passive"))
      (node (ref "IC5") (pin "2") (pinfunction "~{TRIGGER}_2") (pintype "passive"))
      (node (ref "IC5") (pin "6") (pinfunction "THRESHOLD_6") (pintype "passive"))
      (node (ref "R12") (pin "1") (pintype "passive"))
      (node (ref "R19") (pin "1") (pintype "passive"))
      (node (ref "VR2") (pin "1") (pinfunction "CCW_1") (pintype "passive"))
    )
    (net (code "49") (name "Net-(K2-Pad1)") (class "Default")
      (node (ref "K2") (pin "1") (pinfunction "1_1") (pintype "passive"))
      (node (ref "R25") (pin "2") (pintype "passive"))
    )
    (net (code "50") (name "Net-(LED1-A)") (class "Default")
      (node (ref "LED1") (pin "2") (pinfunction "A_2") (pintype "passive"))
      (node (ref "R3") (pin "2") (pintype "passive"))
    )
    (net (code "51") (name "Net-(LED1-K)") (class "Default")
      (node (ref "BZ1") (pin "2") (pinfunction "2_2") (pintype "passive"))
      (node (ref "LED1") (pin "1") (pinfunction "K_1") (pintype "passive"))
      (node (ref "T1") (pin "1") (pinfunction "C_1") (pintype "passive"))
    )
    (net (code "52") (name "Net-(R22-Pad2)") (class "Default")
      (node (ref "R22") (pin "2") (pintype "passive"))
      (node (ref "R24") (pin "1") (pintype "passive"))
    )
    (net (code "53") (name "Net-(T1-B)") (class "Default")
      (node (ref "R7") (pin "1") (pintype "passive"))
      (node (ref "T1") (pin "2") (pinfunction "B_2") (pintype "passive"))
    )
    (net (code "54") (name "Net-(T2-B)") (class "Default")
      (node (ref "R17") (pin "1") (pintype "passive"))
      (node (ref "T2") (pin "2") (pinfunction "B_2") (pintype "passive"))
    )
    (net (code "55") (name "Net-(T2-E)") (class "Default")
      (node (ref "R20") (pin "1") (pintype "passive"))
      (node (ref "T2") (pin "3") (pinfunction "E_3") (pintype "passive"))
    )
    (net (code "56") (name "Net-(T3-B)") (class "Default")
      (node (ref "R12") (pin "2") (pintype "passive"))
      (node (ref "R22") (pin "1") (pintype "passive"))
      (node (ref "T3") (pin "2") (pinfunction "B_2") (pintype "passive"))
    )
    (net (code "57") (name "Net-(T6-G)") (class "Default")
      (node (ref "R1") (pin "1") (pintype "passive"))
      (node (ref "T6") (pin "1") (pinfunction "G_1") (pintype "passive"))
    )
    (net (code "58") (name "Net-(VR1-WIPER)") (class "Default")
      (node (ref "P1") (pin "3") (pinfunction "3_3") (pintype "passive"))
      (node (ref "VR1") (pin "2") (pinfunction "WIPER_2") (pintype "passive"))
    )
    (net (code "59") (name "Ub") (class "Default")
      (node (ref "D6") (pin "1") (pinfunction "K_1") (pintype "passive"))
      (node (ref "IC2") (pin "1") (pinfunction "VIN_1") (pintype "passive"))
      (node (ref "J1") (pin "7") (pinfunction "7_7") (pintype "passive"))
      (node (ref "J2") (pin "7") (pinfunction "7_7") (pintype "passive"))
      (node (ref "J3") (pin "7") (pinfunction "7_7") (pintype "passive"))
      (node (ref "J4") (pin "7") (pinfunction "7_7") (pintype "passive"))
    )
    (net (code "60") (name "unconnected-(1-CLK-Pad38)") (class "Default")
      (node (ref "1") (pin "38") (pinfunction "CLK_38") (pintype "input+no_connect"))
    )
    (net (code "61") (name "unconnected-(1-CMD-Pad18)") (class "Default")
      (node (ref "1") (pin "18") (pinfunction "CMD_18") (pintype "bidirectional"))
    )
    (net (code "62") (name "unconnected-(1-EN-Pad2)") (class "Default")
      (node (ref "1") (pin "2") (pinfunction "EN_2") (pintype "input+no_connect"))
    )
    (net (code "63") (name "unconnected-(1-IO0-Pad33)") (class "Default")
      (node (ref "1") (pin "33") (pinfunction "IO0_33") (pintype "bidirectional"))
    )
    (net (code "64") (name "unconnected-(1-IO2-Pad34)") (class "Default")
      (node (ref "1") (pin "34") (pinfunction "IO2_34") (pintype "bidirectional"))
    )
    (net (code "65") (name "unconnected-(1-IO4-Pad32)") (class "Default")
      (node (ref "1") (pin "32") (pinfunction "IO4_32") (pintype "bidirectional"))
    )
    (net (code "66") (name "unconnected-(1-IO5-Pad29)") (class "Default")
      (node (ref "1") (pin "29") (pinfunction "IO5_29") (pintype "bidirectional"))
    )
    (net (code "67") (name "unconnected-(1-IO12-Pad13)") (class "Default")
      (node (ref "1") (pin "13") (pinfunction "IO12_13") (pintype "bidirectional"))
    )
    (net (code "68") (name "unconnected-(1-IO13-Pad15)") (class "Default")
      (node (ref "1") (pin "15") (pinfunction "IO13_15") (pintype "bidirectional"))
    )
    (net (code "69") (name "unconnected-(1-IO14-Pad12)") (class "Default")
      (node (ref "1") (pin "12") (pinfunction "IO14_12") (pintype "bidirectional"))
    )
    (net (code "70") (name "unconnected-(1-IO18-Pad28)") (class "Default")
      (node (ref "1") (pin "28") (pinfunction "IO18_28") (pintype "bidirectional"))
    )
    (net (code "71") (name "unconnected-(1-IO19-Pad27)") (class "Default")
      (node (ref "1") (pin "27") (pinfunction "IO19_27") (pintype "bidirectional"))
    )
    (net (code "72") (name "unconnected-(1-IO23-Pad21)") (class "Default")
      (node (ref "1") (pin "21") (pinfunction "IO23_21") (pintype "bidirectional"))
    )
    (net (code "73") (name "unconnected-(1-IO25-Pad9)") (class "Default")
      (node (ref "1") (pin "9") (pinfunction "IO25_9") (pintype "bidirectional"))
    )
    (net (code "74") (name "unconnected-(1-IO32-Pad7)") (class "Default")
      (node (ref "1") (pin "7") (pinfunction "IO32_7") (pintype "bidirectional"))
    )
    (net (code "75") (name "unconnected-(1-IO33-Pad8)") (class "Default")
      (node (ref "1") (pin "8") (pinfunction "IO33_8") (pintype "bidirectional"))
    )
    (net (code "76") (name "unconnected-(1-IO35-Pad6)") (class "Default")
      (node (ref "1") (pin "6") (pinfunction "IO35_6") (pintype "bidirectional"))
    )
    (net (code "77") (name "unconnected-(1-RXD0-Pad24)") (class "Default")
      (node (ref "1") (pin "24") (pinfunction "RXD0_24") (pintype "input+no_connect"))
    )
    (net (code "78") (name "unconnected-(1-SD0-Pad37)") (class "Default")
      (node (ref "1") (pin "37") (pinfunction "SD0_37") (pintype "bidirectional"))
    )
    (net (code "79") (name "unconnected-(1-SD1-Pad36)") (class "Default")
      (node (ref "1") (pin "36") (pinfunction "SD1_36") (pintype "bidirectional"))
    )
    (net (code "80") (name "unconnected-(1-SD2-Pad16)") (class "Default")
      (node (ref "1") (pin "16") (pinfunction "SD2_16") (pintype "bidirectional"))
    )
    (net (code "81") (name "unconnected-(1-SD3-Pad17)") (class "Default")
      (node (ref "1") (pin "17") (pinfunction "SD3_17") (pintype "bidirectional"))
    )
    (net (code "82") (name "unconnected-(1-SENSOR_VN-Pad4)") (class "Default")
      (node (ref "1") (pin "4") (pinfunction "SENSOR_VN_4") (pintype "input+no_connect"))
    )
    (net (code "83") (name "unconnected-(1-SENSOR_VP-Pad3)") (class "Default")
      (node (ref "1") (pin "3") (pinfunction "SENSOR_VP_3") (pintype "input+no_connect"))
    )
    (net (code "84") (name "unconnected-(1-TXD0-Pad23)") (class "Default")
      (node (ref "1") (pin "23") (pinfunction "TXD0_23") (pintype "output"))
    )
    (net (code "85") (name "unconnected-(IC1D-G-Pad12)") (class "Default")
      (node (ref "IC1") (pin "12") (pinfunction "G_12") (pintype "input+no_connect"))
    )
    (net (code "86") (name "unconnected-(IC1D-H-Pad13)") (class "Default")
      (node (ref "IC1") (pin "13") (pinfunction "H_13") (pintype "input+no_connect"))
    )
    (net (code "87") (name "unconnected-(IC1D-M-Pad11)") (class "Default")
      (node (ref "IC1") (pin "11") (pinfunction "M_11") (pintype "output+no_connect"))
    )
    (net (code "88") (name "unconnected-(IC3-NC-Pad1)") (class "Default")
      (node (ref "IC3") (pin "1") (pinfunction "NC_1") (pintype "passive"))
    )
    (net (code "89") (name "unconnected-(IC3-NC-Pad5)") (class "Default")
      (node (ref "IC3") (pin "5") (pinfunction "NC_5") (pintype "passive"))
    )
    (net (code "90") (name "unconnected-(IC4-P3-Pad7)") (class "Default")
      (node (ref "IC4") (pin "7") (pinfunction "P3_7") (pintype "bidirectional"))
    )
    (net (code "91") (name "unconnected-(IC4-~{INT}-Pad13)") (class "Default")
      (node (ref "IC4") (pin "13") (pinfunction "~{INT}_13") (pintype "open_collector"))
    )
    (net (code "92") (name "unconnected-(P1-Pad8)") (class "Default")
      (node (ref "P1") (pin "8") (pinfunction "8_8") (pintype "passive"))
    )
    (net (code "93") (name "unconnected-(P1-Pad9)") (class "Default")
      (node (ref "P1") (pin "9") (pinfunction "9_9") (pintype "passive"))
    )
    (net (code "94") (name "unconnected-(P1-Pad10)") (class "Default")
      (node (ref "P1") (pin "10") (pinfunction "10_10") (pintype "passive"))
    )
    (net (code "95") (name "unconnected-(P1-Pad17)") (class "Default")
      (node (ref "P1") (pin "17") (pinfunction "17_17") (pintype "passive"))
    )
    (net (code "96") (name "unconnected-(P1-Pad18)") (class "Default")
      (node (ref "P1") (pin "18") (pinfunction "18_18") (pintype "passive"))
    )
    (net (code "97") (name "unconnected-(P1-Pad19)") (class "Default")
      (node (ref "P1") (pin "19") (pinfunction "19_19") (pintype "passive"))
    )
    (net (code "98") (name "unconnected-(P1-Pad20)") (class "Default")
      (node (ref "P1") (pin "20") (pinfunction "20_20") (pintype "passive"))
    )
  )
)
